# opendecoder.net
KiCad netlist of a schematic drawn in EAGLE
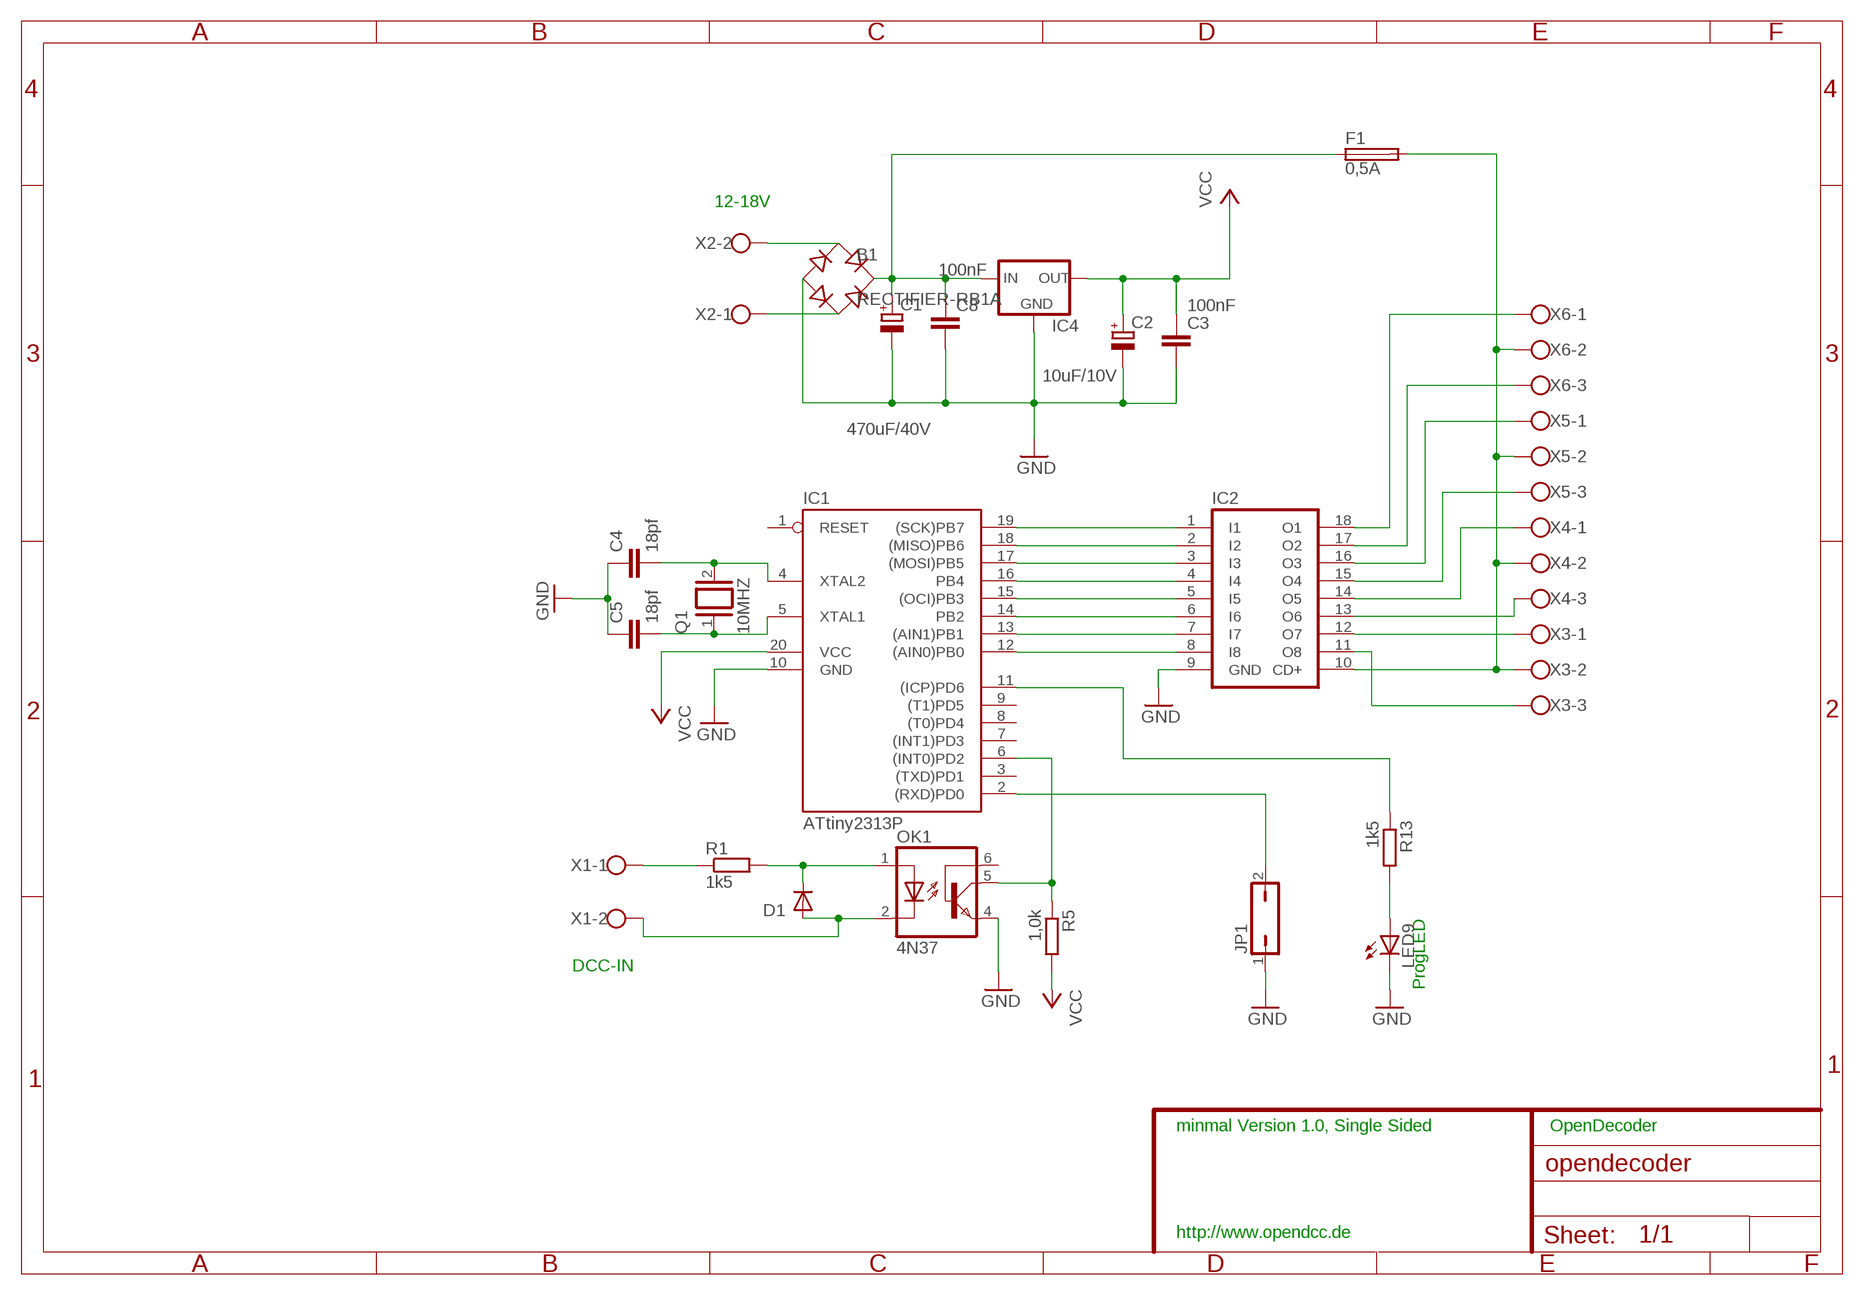
[diagram p0: schematic, sheet 1]

(export (version "E")
  (design (tool "Eeschema 10.0.6"))
  (components
    (comp (ref "B1")
      (value "RECTIFIER-RB1A")
      (footprint "eagle-import:RB1A")
      (libsource (lib "eagle-import") (part "RECTIFIER-RB1A"))
    )
    (comp (ref "C1")
      (value "470uF/40V")
      (footprint "eagle-import:E5-10,5")
      (libsource (lib "eagle-import") (part "CPOL-EUE5-10.5"))
    )
    (comp (ref "C2")
      (value "10uF/10V")
      (footprint "eagle-import:E5-6")
      (libsource (lib "eagle-import") (part "CPOL-EUE5-6"))
    )
    (comp (ref "C3")
      (value "100nF")
      (footprint "eagle-import:C025_050-025X075")
      (libsource (lib "eagle-import") (part "C-EU025_050-025X075"))
    )
    (comp (ref "C4")
      (value "18pf")
      (footprint "eagle-import:C025-025X050")
      (libsource (lib "eagle-import") (part "C-EU025-025X050"))
    )
    (comp (ref "C5")
      (value "18pf")
      (footprint "eagle-import:C025-025X050")
      (libsource (lib "eagle-import") (part "C-EU025-025X050"))
    )
    (comp (ref "C8")
      (value "100nF")
      (footprint "eagle-import:C050-024X044")
      (libsource (lib "eagle-import") (part "C-EU050-024X044"))
    )
    (comp (ref "D1")
      (value "DIODE-D-2.5")
      (footprint "eagle-import:D-2.5")
      (libsource (lib "eagle-import") (part "DIODE-D-2.5"))
    )
    (comp (ref "F1")
      (value "0,5A")
      (footprint "eagle-import:TE5")
      (libsource (lib "eagle-import") (part "TE5"))
    )
    (comp (ref "IC1")
      (value "ATtiny2313P")
      (footprint "eagle-import:DIL20")
      (libsource (lib "eagle-import") (part "AT90S2313P"))
    )
    (comp (ref "IC2")
      (value "ULN2803A")
      (footprint "eagle-import:DIL18")
      (libsource (lib "eagle-import") (part "ULN2803A"))
    )
    (comp (ref "IC4")
      (value "78XXS")
      (footprint "eagle-import:78XXS")
      (libsource (lib "eagle-import") (part "78XXS"))
    )
    (comp (ref "JP1")
      (value "JP1Q")
      (footprint "eagle-import:JP1")
      (libsource (lib "eagle-import") (part "JP1Q"))
    )
    (comp (ref "LED9")
      (value "LED3MM")
      (footprint "eagle-import:LED3MM")
      (libsource (lib "eagle-import") (part "LED3MM"))
    )
    (comp (ref "OK1")
      (value "4N37")
      (footprint "eagle-import:DIL06")
      (fields (field (name "MF") "FAIRCHILD SEMICONDUCTOR"))
      (libsource (lib "eagle-import") (part "4N37"))
    )
    (comp (ref "Q1")
      (value "10MHZ")
      (footprint "eagle-import:QS")
      (libsource (lib "eagle-import") (part "XTAL/S"))
    )
    (comp (ref "R1")
      (value "1k5")
      (footprint "eagle-import:0204V")
      (libsource (lib "eagle-import") (part "R-EU_0204/2V"))
    )
    (comp (ref "R5")
      (value "1,0k")
      (footprint "eagle-import:0207_2V")
      (libsource (lib "eagle-import") (part "R-EU_0207/2V"))
    )
    (comp (ref "R13")
      (value "1k5")
      (footprint "eagle-import:0204V")
      (libsource (lib "eagle-import") (part "R-EU_0204/2V"))
    )
    (comp (ref "X1")
      (value "AK550/2")
      (footprint "eagle-import:AK550_2")
      (libsource (lib "eagle-import") (part "AK550/2"))
    )
    (comp (ref "X2")
      (value "AK550/2")
      (footprint "eagle-import:AK550_2")
      (libsource (lib "eagle-import") (part "AK550/2"))
    )
    (comp (ref "X3")
      (value "AK550/3")
      (footprint "eagle-import:AK550_3")
      (libsource (lib "eagle-import") (part "AK550/3"))
    )
    (comp (ref "X4")
      (value "AK550/3")
      (footprint "eagle-import:AK550_3")
      (libsource (lib "eagle-import") (part "AK550/3"))
    )
    (comp (ref "X5")
      (value "AK550/3")
      (footprint "eagle-import:AK550_3")
      (libsource (lib "eagle-import") (part "AK550/3"))
    )
    (comp (ref "X6")
      (value "AK550/3")
      (footprint "eagle-import:AK550_3")
      (libsource (lib "eagle-import") (part "AK550/3"))
    )
  )
  (nets
    (net (code "1") (name "GND") (class "Default")
      (node (ref "B1") (pin "-") (pinfunction "-_-") (pintype "passive"))
      (node (ref "C1") (pin "-") (pinfunction "-_-") (pintype "passive"))
      (node (ref "C2") (pin "-") (pinfunction "-_-") (pintype "passive"))
      (node (ref "C3") (pin "2") (pinfunction "2_2") (pintype "passive"))
      (node (ref "C4") (pin "1") (pinfunction "1_1") (pintype "passive"))
      (node (ref "C5") (pin "1") (pinfunction "1_1") (pintype "passive"))
      (node (ref "C8") (pin "2") (pinfunction "2_2") (pintype "passive"))
      (node (ref "IC1") (pin "10") (pinfunction "GND_10") (pintype "power_in"))
      (node (ref "IC2") (pin "9") (pinfunction "GND_9") (pintype "power_in"))
      (node (ref "IC4") (pin "GND") (pinfunction "GND_GND") (pintype "input"))
      (node (ref "JP1") (pin "1") (pinfunction "1_1") (pintype "passive"))
      (node (ref "LED9") (pin "K") (pinfunction "C_K") (pintype "passive"))
      (node (ref "OK1") (pin "4") (pinfunction "EMI_4") (pintype "passive"))
    )
    (net (code "2") (name "Net-(B1-Pad+)") (class "Default")
      (node (ref "B1") (pin "+") (pinfunction "+_+") (pintype "passive"))
      (node (ref "C1") (pin "+") (pinfunction "+_+") (pintype "passive"))
      (node (ref "C8") (pin "1") (pinfunction "1_1") (pintype "passive"))
      (node (ref "F1") (pin "1") (pinfunction "1_1") (pintype "passive"))
      (node (ref "IC4") (pin "IN") (pinfunction "IN_IN") (pintype "input"))
    )
    (net (code "3") (name "Net-(IC1-(AIN0)PB0)") (class "Default")
      (node (ref "IC1") (pin "12") (pinfunction "(AIN0)PB0_12") (pintype "bidirectional"))
      (node (ref "IC2") (pin "8") (pinfunction "I8_8") (pintype "input"))
    )
    (net (code "4") (name "Net-(IC1-(AIN1)PB1)") (class "Default")
      (node (ref "IC1") (pin "13") (pinfunction "(AIN1)PB1_13") (pintype "bidirectional"))
      (node (ref "IC2") (pin "7") (pinfunction "I7_7") (pintype "input"))
    )
    (net (code "5") (name "Net-(IC1-(ICP)PD6)") (class "Default")
      (node (ref "IC1") (pin "11") (pinfunction "(ICP)PD6_11") (pintype "bidirectional"))
      (node (ref "R13") (pin "1") (pinfunction "1_1") (pintype "passive"))
    )
    (net (code "6") (name "Net-(IC1-(INT0)PD2)") (class "Default")
      (node (ref "IC1") (pin "6") (pinfunction "(INT0)PD2_6") (pintype "bidirectional"))
      (node (ref "OK1") (pin "5") (pinfunction "COL_5") (pintype "passive"))
      (node (ref "R5") (pin "1") (pinfunction "1_1") (pintype "passive"))
    )
    (net (code "7") (name "Net-(IC1-(MISO)PB6)") (class "Default")
      (node (ref "IC1") (pin "18") (pinfunction "(MISO)PB6_18") (pintype "bidirectional"))
      (node (ref "IC2") (pin "2") (pinfunction "I2_2") (pintype "input"))
    )
    (net (code "8") (name "Net-(IC1-(MOSI)PB5)") (class "Default")
      (node (ref "IC1") (pin "17") (pinfunction "(MOSI)PB5_17") (pintype "bidirectional"))
      (node (ref "IC2") (pin "3") (pinfunction "I3_3") (pintype "input"))
    )
    (net (code "9") (name "Net-(IC1-(OCI)PB3)") (class "Default")
      (node (ref "IC1") (pin "15") (pinfunction "(OCI)PB3_15") (pintype "bidirectional"))
      (node (ref "IC2") (pin "5") (pinfunction "I5_5") (pintype "input"))
    )
    (net (code "10") (name "Net-(IC1-(RXD)PD0)") (class "Default")
      (node (ref "IC1") (pin "2") (pinfunction "(RXD)PD0_2") (pintype "bidirectional"))
      (node (ref "JP1") (pin "2") (pinfunction "2_2") (pintype "passive"))
    )
    (net (code "11") (name "Net-(IC1-(SCK)PB7)") (class "Default")
      (node (ref "IC1") (pin "19") (pinfunction "(SCK)PB7_19") (pintype "bidirectional"))
      (node (ref "IC2") (pin "1") (pinfunction "I1_1") (pintype "input"))
    )
    (net (code "12") (name "Net-(IC1-PB2)") (class "Default")
      (node (ref "IC1") (pin "14") (pinfunction "PB2_14") (pintype "bidirectional"))
      (node (ref "IC2") (pin "6") (pinfunction "I6_6") (pintype "input"))
    )
    (net (code "13") (name "Net-(IC1-PB4)") (class "Default")
      (node (ref "IC1") (pin "16") (pinfunction "PB4_16") (pintype "bidirectional"))
      (node (ref "IC2") (pin "4") (pinfunction "I4_4") (pintype "input"))
    )
    (net (code "14") (name "Net-(IC1-XTAL1)") (class "Default")
      (node (ref "C5") (pin "2") (pinfunction "2_2") (pintype "passive"))
      (node (ref "IC1") (pin "5") (pinfunction "XTAL1_5") (pintype "bidirectional"))
      (node (ref "Q1") (pin "1") (pinfunction "1_1") (pintype "passive"))
    )
    (net (code "15") (name "Net-(IC1-XTAL2)") (class "Default")
      (node (ref "C4") (pin "2") (pinfunction "2_2") (pintype "passive"))
      (node (ref "IC1") (pin "4") (pinfunction "XTAL2_4") (pintype "bidirectional"))
      (node (ref "Q1") (pin "2") (pinfunction "2_2") (pintype "passive"))
    )
    (net (code "16") (name "Net-(IC2-CD+)") (class "Default")
      (node (ref "F1") (pin "2") (pinfunction "2_2") (pintype "passive"))
      (node (ref "IC2") (pin "10") (pinfunction "CD+_10") (pintype "passive"))
      (node (ref "X3") (pin "2") (pinfunction "KL_2") (pintype "passive"))
      (node (ref "X4") (pin "2") (pinfunction "KL_2") (pintype "passive"))
      (node (ref "X5") (pin "2") (pinfunction "KL_2") (pintype "passive"))
      (node (ref "X6") (pin "2") (pinfunction "KL_2") (pintype "passive"))
    )
    (net (code "17") (name "Net-(IC2-O1)") (class "Default")
      (node (ref "IC2") (pin "18") (pinfunction "O1_18") (pintype "open_collector"))
      (node (ref "X6") (pin "1") (pinfunction "KL_1") (pintype "passive"))
    )
    (net (code "18") (name "Net-(IC2-O2)") (class "Default")
      (node (ref "IC2") (pin "17") (pinfunction "O2_17") (pintype "open_collector"))
      (node (ref "X6") (pin "3") (pinfunction "KL_3") (pintype "passive"))
    )
    (net (code "19") (name "Net-(IC2-O3)") (class "Default")
      (node (ref "IC2") (pin "16") (pinfunction "O3_16") (pintype "open_collector"))
      (node (ref "X5") (pin "1") (pinfunction "KL_1") (pintype "passive"))
    )
    (net (code "20") (name "Net-(IC2-O4)") (class "Default")
      (node (ref "IC2") (pin "15") (pinfunction "O4_15") (pintype "open_collector"))
      (node (ref "X5") (pin "3") (pinfunction "KL_3") (pintype "passive"))
    )
    (net (code "21") (name "Net-(IC2-O5)") (class "Default")
      (node (ref "IC2") (pin "14") (pinfunction "O5_14") (pintype "open_collector"))
      (node (ref "X4") (pin "1") (pinfunction "KL_1") (pintype "passive"))
    )
    (net (code "22") (name "Net-(IC2-O6)") (class "Default")
      (node (ref "IC2") (pin "13") (pinfunction "O6_13") (pintype "open_collector"))
      (node (ref "X4") (pin "3") (pinfunction "KL_3") (pintype "passive"))
    )
    (net (code "23") (name "Net-(IC2-O7)") (class "Default")
      (node (ref "IC2") (pin "12") (pinfunction "O7_12") (pintype "open_collector"))
      (node (ref "X3") (pin "1") (pinfunction "KL_1") (pintype "passive"))
    )
    (net (code "24") (name "Net-(IC2-O8)") (class "Default")
      (node (ref "IC2") (pin "11") (pinfunction "O8_11") (pintype "open_collector"))
      (node (ref "X3") (pin "3") (pinfunction "KL_3") (pintype "passive"))
    )
    (net (code "25") (name "Net-(LED9-PadA)") (class "Default")
      (node (ref "LED9") (pin "A") (pinfunction "A_A") (pintype "passive"))
      (node (ref "R13") (pin "2") (pinfunction "2_2") (pintype "passive"))
    )
    (net (code "26") (name "Net-(OK1-A)") (class "Default")
      (node (ref "D1") (pin "C") (pinfunction "C_C") (pintype "passive"))
      (node (ref "OK1") (pin "1") (pinfunction "A_1") (pintype "passive"))
      (node (ref "R1") (pin "2") (pinfunction "2_2") (pintype "passive"))
    )
    (net (code "27") (name "Net-(OK1-C)") (class "Default")
      (node (ref "D1") (pin "A") (pinfunction "A_A") (pintype "passive"))
      (node (ref "OK1") (pin "2") (pinfunction "C_2") (pintype "passive"))
      (node (ref "X1") (pin "2") (pinfunction "KL_2") (pintype "passive"))
    )
    (net (code "28") (name "Net-(X1A-KL)") (class "Default")
      (node (ref "R1") (pin "1") (pinfunction "1_1") (pintype "passive"))
      (node (ref "X1") (pin "1") (pinfunction "KL_1") (pintype "passive"))
    )
    (net (code "29") (name "Net-(X2A-KL)") (class "Default")
      (node (ref "B1") (pin "AC2") (pinfunction "AC2_AC2") (pintype "passive"))
      (node (ref "X2") (pin "1") (pinfunction "KL_1") (pintype "passive"))
    )
    (net (code "30") (name "Net-(X2B-KL)") (class "Default")
      (node (ref "B1") (pin "AC1") (pinfunction "AC1_AC1") (pintype "passive"))
      (node (ref "X2") (pin "2") (pinfunction "KL_2") (pintype "passive"))
    )
    (net (code "31") (name "VCC") (class "Default")
      (node (ref "C2") (pin "+") (pinfunction "+_+") (pintype "passive"))
      (node (ref "C3") (pin "1") (pinfunction "1_1") (pintype "passive"))
      (node (ref "IC1") (pin "20") (pinfunction "VCC_20") (pintype "power_in"))
      (node (ref "IC4") (pin "OUT") (pinfunction "OUT_OUT") (pintype "passive"))
      (node (ref "R5") (pin "2") (pinfunction "2_2") (pintype "passive"))
    )
    (net (code "32") (name "unconnected-(IC1-(INT1)PD3-Pad7)") (class "Default")
      (node (ref "IC1") (pin "7") (pinfunction "(INT1)PD3_7") (pintype "bidirectional"))
    )
    (net (code "33") (name "unconnected-(IC1-(T0)PD4-Pad8)") (class "Default")
      (node (ref "IC1") (pin "8") (pinfunction "(T0)PD4_8") (pintype "bidirectional"))
    )
    (net (code "34") (name "unconnected-(IC1-(T1)PD5-Pad9)") (class "Default")
      (node (ref "IC1") (pin "9") (pinfunction "(T1)PD5_9") (pintype "bidirectional"))
    )
    (net (code "35") (name "unconnected-(IC1-(TXD)PD1-Pad3)") (class "Default")
      (node (ref "IC1") (pin "3") (pinfunction "(TXD)PD1_3") (pintype "bidirectional"))
    )
    (net (code "36") (name "unconnected-(IC1-RESET-Pad1)") (class "Default")
      (node (ref "IC1") (pin "1") (pinfunction "RESET_1") (pintype "bidirectional"))
    )
    (net (code "37") (name "unconnected-(OK1-BAS-Pad6)") (class "Default")
      (node (ref "OK1") (pin "6") (pinfunction "BAS_6") (pintype "passive"))
    )
  )
)
